# Boutconectie.net
KiCad netlist of a schematic drawn in Altium Designer
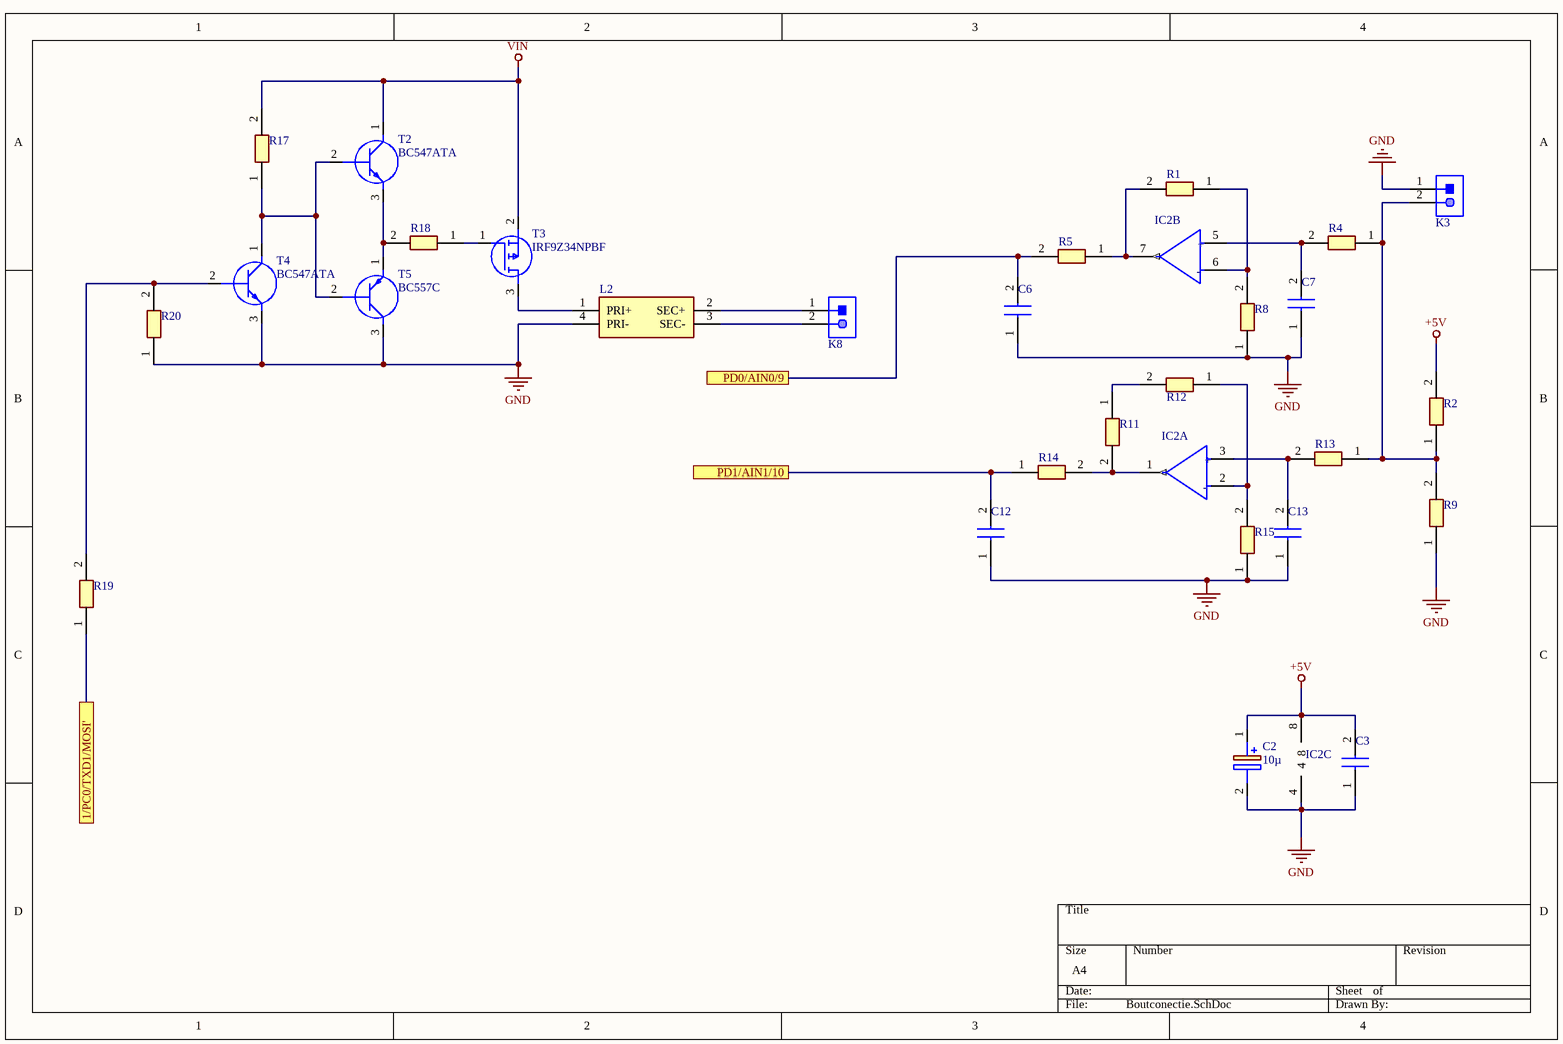
[diagram p0: Boutconectie.SchDoc]

(export (version "E")
  (design (tool "Eeschema 10.0.6"))
  (components
    (comp (ref "C2")
      (value "10µ")
      (footprint "SamacSys:CAPPRD200W52D500H1250")
      (description "Capacitor Polarised")
      (fields
        (field (name "MANUFACTURER_PART_NUMBER") "860010672009")
        (field (name "MOUSER PART NUMBER") "710-860010672009")
      )
      (libsource (lib "*") (part "860010672009"))
    )
    (comp (ref "C3")
      (value "~")
      (footprint "SamacSys:CAPC2012X95N")
      (description "Capacitor")
      (fields (field (name "MANUFACTURER_PART_NUMBER") "CC0805KPX7R9BB104"))
      (libsource (lib "*") (part "CC0805KPX7R9BB104"))
    )
    (comp (ref "C6")
      (value "~")
      (footprint "SamacSys:CAPC2012X95N")
      (description "Capacitor")
      (fields (field (name "MANUFACTURER_PART_NUMBER") "CC0805KPX7R9BB104"))
      (libsource (lib "*") (part "CC0805KPX7R9BB104"))
    )
    (comp (ref "C7")
      (value "~")
      (footprint "SamacSys:CAPC2012X95N")
      (description "Capacitor")
      (fields (field (name "MANUFACTURER_PART_NUMBER") "CC0805KPX7R9BB104"))
      (libsource (lib "*") (part "CC0805KPX7R9BB104"))
    )
    (comp (ref "C12")
      (value "~")
      (footprint "SamacSys:CAPC2012X95N")
      (description "Capacitor")
      (fields (field (name "MANUFACTURER_PART_NUMBER") "CC0805KPX7R9BB104"))
      (libsource (lib "*") (part "CC0805KPX7R9BB104"))
    )
    (comp (ref "C13")
      (value "~")
      (footprint "SamacSys:CAPC2012X95N")
      (description "Capacitor")
      (fields (field (name "MANUFACTURER_PART_NUMBER") "CC0805KPX7R9BB104"))
      (libsource (lib "*") (part "CC0805KPX7R9BB104"))
    )
    (comp (ref "IC2")
      (value "MCP6002-E_P")
      (footprint "SamacSys:DIP781W56P254L950H533Q8N")
      (description "Integrated Circuit")
      (fields
        (field (name "MANUFACTURER_PART_NUMBER") "MCP6002-E/P")
        (field (name "MOUSER PART NUMBER") "579-MCP6002-E/P")
      )
      (libsource (lib "SoldeerBoutLib") (part "MCP6002-E_P"))
    )
    (comp (ref "K3")
      (value "620102131822")
      (footprint "620102131822")
      (description "Male Shrouded Header WR-WTB, SMT, Right Angled, pitch 2 mm, 1 x 2 position")
      (fields (field (name "MANUFACTURER") "Wurth Elektronik") (field (name "PUBLISHER") "WurthElektronik"))
      (libsource (lib "Altium Content Vault") (part "WE-CN-1P-M-R2"))
    )
    (comp (ref "K8")
      (value "620102131822")
      (footprint "620102131822")
      (description "Male Shrouded Header WR-WTB, SMT, Right Angled, pitch 2 mm, 1 x 2 position")
      (fields (field (name "MANUFACTURER") "Wurth Elektronik") (field (name "PUBLISHER") "WurthElektronik"))
      (libsource (lib "Altium Content Vault") (part "WE-CN-1P-M-R2"))
    )
    (comp (ref "L2")
      (value "CM2545X171B-10")
      (footprint "SamacSys:CM2545X171B10")
      (description "Transformer")
      (libsource (lib "SoldeerBoutLib") (part "CM2545X171B-10"))
    )
    (comp (ref "R1")
      (value "~")
      (footprint "SamacSys:RESC2012X90N")
      (description "Resistor")
      (fields (field (name "MANUFACTURER_PART_NUMBER") "CFN0805-JZ-R010ELF"))
      (libsource (lib "SoldeerBoutLib") (part "CFN0805-JZ-R010ELF"))
    )
    (comp (ref "R2")
      (value "~")
      (footprint "SamacSys:RESC2012X90N")
      (description "Resistor")
      (fields (field (name "MANUFACTURER_PART_NUMBER") "CFN0805-JZ-R010ELF"))
      (libsource (lib "") (part "CFN0805-JZ-R010ELF_1"))
    )
    (comp (ref "R4")
      (value "~")
      (footprint "SamacSys:RESC2012X90N")
      (description "Resistor")
      (fields (field (name "MANUFACTURER_PART_NUMBER") "CFN0805-JZ-R010ELF"))
      (libsource (lib "SoldeerBoutLib") (part "CFN0805-JZ-R010ELF"))
    )
    (comp (ref "R5")
      (value "~")
      (footprint "SamacSys:RESC2012X90N")
      (description "Resistor")
      (fields (field (name "MANUFACTURER_PART_NUMBER") "CFN0805-JZ-R010ELF"))
      (libsource (lib "SoldeerBoutLib") (part "CFN0805-JZ-R010ELF"))
    )
    (comp (ref "R8")
      (value "~")
      (footprint "SamacSys:RESC2012X90N")
      (description "Resistor")
      (fields (field (name "MANUFACTURER_PART_NUMBER") "CFN0805-JZ-R010ELF"))
      (libsource (lib "") (part "CFN0805-JZ-R010ELF_1"))
    )
    (comp (ref "R9")
      (value "~")
      (footprint "SamacSys:RESC2012X90N")
      (description "Resistor")
      (fields (field (name "MANUFACTURER_PART_NUMBER") "CFN0805-JZ-R010ELF"))
      (libsource (lib "") (part "CFN0805-JZ-R010ELF_1"))
    )
    (comp (ref "R11")
      (value "~")
      (footprint "SamacSys:RESC2012X90N")
      (description "Resistor")
      (fields (field (name "MANUFACTURER_PART_NUMBER") "CFN0805-JZ-R010ELF"))
      (libsource (lib "") (part "CFN0805-JZ-R010ELF_2"))
    )
    (comp (ref "R12")
      (value "~")
      (footprint "SamacSys:RESC2012X90N")
      (description "Resistor")
      (fields (field (name "MANUFACTURER_PART_NUMBER") "CFN0805-JZ-R010ELF"))
      (libsource (lib "SoldeerBoutLib") (part "CFN0805-JZ-R010ELF"))
    )
    (comp (ref "R13")
      (value "~")
      (footprint "SamacSys:RESC2012X90N")
      (description "Resistor")
      (fields (field (name "MANUFACTURER_PART_NUMBER") "CFN0805-JZ-R010ELF"))
      (libsource (lib "SoldeerBoutLib") (part "CFN0805-JZ-R010ELF"))
    )
    (comp (ref "R14")
      (value "~")
      (footprint "SamacSys:RESC2012X90N")
      (description "Resistor")
      (fields (field (name "MANUFACTURER_PART_NUMBER") "CFN0805-JZ-R010ELF"))
      (libsource (lib "") (part "CFN0805-JZ-R010ELF_3"))
    )
    (comp (ref "R15")
      (value "~")
      (footprint "SamacSys:RESC2012X90N")
      (description "Resistor")
      (fields (field (name "MANUFACTURER_PART_NUMBER") "CFN0805-JZ-R010ELF"))
      (libsource (lib "") (part "CFN0805-JZ-R010ELF_1"))
    )
    (comp (ref "R17")
      (value "~")
      (footprint "SamacSys:RESC2012X90N")
      (description "Resistor")
      (fields (field (name "MANUFACTURER_PART_NUMBER") "CFN0805-JZ-R010ELF"))
      (libsource (lib "") (part "CFN0805-JZ-R010ELF_1"))
    )
    (comp (ref "R18")
      (value "~")
      (footprint "SamacSys:RESC2012X90N")
      (description "Resistor")
      (fields (field (name "MANUFACTURER_PART_NUMBER") "CFN0805-JZ-R010ELF"))
      (libsource (lib "SoldeerBoutLib") (part "CFN0805-JZ-R010ELF"))
    )
    (comp (ref "R19")
      (value "~")
      (footprint "SamacSys:RESC2012X90N")
      (description "Resistor")
      (fields (field (name "MANUFACTURER_PART_NUMBER") "CFN0805-JZ-R010ELF"))
      (libsource (lib "") (part "CFN0805-JZ-R010ELF_1"))
    )
    (comp (ref "R20")
      (value "~")
      (footprint "SamacSys:RESC2012X90N")
      (description "Resistor")
      (fields (field (name "MANUFACTURER_PART_NUMBER") "CFN0805-JZ-R010ELF"))
      (libsource (lib "") (part "CFN0805-JZ-R010ELF_1"))
    )
    (comp (ref "T2")
      (value "BC547ATA")
      (footprint "SamacSys:TO-92_(TO-226)")
      (description "Transistor BJT NPN")
      (fields (field (name "MOUSER PART NUMBER") "512-BC547ATA"))
      (libsource (lib "*") (part "BC547ATA"))
    )
    (comp (ref "T3")
      (value "IRF9Z34NPBF")
      (footprint "SamacSys:TO254P469X1042X1967-3P")
      (description "MOSFET (P-Channel)")
      (fields (field (name "MOUSER PART NUMBER") "942-IRF9Z34NPBF"))
      (libsource (lib "SoldeerBoutLib") (part "IRF9Z34NPBF"))
    )
    (comp (ref "T4")
      (value "BC547ATA")
      (footprint "SamacSys:TO-92_(TO-226)")
      (description "Transistor BJT NPN")
      (fields (field (name "MOUSER PART NUMBER") "512-BC547ATA"))
      (libsource (lib "*") (part "BC547ATA"))
    )
    (comp (ref "T5")
      (value "BC557C")
      (footprint "SamacSys:BC557C")
      (description "Transistor BJT PNP")
      (fields (field (name "MOUSER PART NUMBER") "771-BC557C"))
      (libsource (lib "SoldeerBoutLib") (part "BC557C"))
    )
  )
  (nets
    (net (code "1") (name "+5V") (class "Default")
      (node (ref "C2") (pin "1") (pinfunction "+_1") (pintype "passive"))
      (node (ref "C3") (pin "2") (pinfunction "2_2") (pintype "passive"))
      (node (ref "IC2") (pin "8") (pinfunction "8_8") (pintype "passive"))
      (node (ref "R2") (pin "2") (pinfunction "2_2") (pintype "passive"))
    )
    (net (code "2") (name "/1{slash}PC0{slash}TXD1{slash}MOSI'") (class "Default")
      (node (ref "R19") (pin "1") (pinfunction "1_1") (pintype "passive"))
    )
    (net (code "3") (name "/PD0{slash}AIN0{slash}9") (class "Default")
      (node (ref "C6") (pin "2") (pinfunction "2_2") (pintype "passive"))
      (node (ref "R5") (pin "2") (pinfunction "2_2") (pintype "passive"))
    )
    (net (code "4") (name "/PD1{slash}AIN1{slash}10") (class "Default")
      (node (ref "C12") (pin "2") (pinfunction "2_2") (pintype "passive"))
      (node (ref "R14") (pin "1") (pinfunction "1_1") (pintype "passive"))
    )
    (net (code "5") (name "GND") (class "Default")
      (node (ref "C12") (pin "1") (pinfunction "1_1") (pintype "passive"))
      (node (ref "C13") (pin "1") (pinfunction "1_1") (pintype "passive"))
      (node (ref "C2") (pin "2") (pinfunction "-_2") (pintype "passive"))
      (node (ref "C3") (pin "1") (pinfunction "1_1") (pintype "passive"))
      (node (ref "C6") (pin "1") (pinfunction "1_1") (pintype "passive"))
      (node (ref "C7") (pin "1") (pinfunction "1_1") (pintype "passive"))
      (node (ref "IC2") (pin "4") (pinfunction "4_4") (pintype "passive"))
      (node (ref "K3") (pin "1") (pinfunction "1_1") (pintype "passive"))
      (node (ref "L2") (pin "4") (pinfunction "PRI-_4") (pintype "passive"))
      (node (ref "R15") (pin "1") (pinfunction "1_1") (pintype "passive"))
      (node (ref "R20") (pin "1") (pinfunction "1_1") (pintype "passive"))
      (node (ref "R8") (pin "1") (pinfunction "1_1") (pintype "passive"))
      (node (ref "R9") (pin "1") (pinfunction "1_1") (pintype "passive"))
      (node (ref "T4") (pin "3") (pinfunction "E_3") (pintype "passive"))
      (node (ref "T5") (pin "3") (pinfunction "C_3") (pintype "passive"))
    )
    (net (code "6") (name "Net-(IC2A-2IN+)") (class "Default")
      (node (ref "C13") (pin "2") (pinfunction "2_2") (pintype "passive"))
      (node (ref "IC2") (pin "3") (pinfunction "2IN+_3") (pintype "tri_state"))
      (node (ref "R13") (pin "2") (pinfunction "2_2") (pintype "passive"))
    )
    (net (code "7") (name "Net-(IC2A-2IN-)") (class "Default")
      (node (ref "IC2") (pin "2") (pinfunction "2IN-_2") (pintype "tri_state"))
      (node (ref "R12") (pin "1") (pinfunction "1_1") (pintype "passive"))
      (node (ref "R15") (pin "2") (pinfunction "2_2") (pintype "passive"))
    )
    (net (code "8") (name "Net-(IC2A-2OUT)") (class "Default")
      (node (ref "IC2") (pin "1") (pinfunction "2OUT_1") (pintype "output"))
      (node (ref "R11") (pin "2") (pinfunction "2_2") (pintype "passive"))
      (node (ref "R14") (pin "2") (pinfunction "2_2") (pintype "passive"))
    )
    (net (code "9") (name "Net-(IC2B-2IN+)") (class "Default")
      (node (ref "C7") (pin "2") (pinfunction "2_2") (pintype "passive"))
      (node (ref "IC2") (pin "5") (pinfunction "2IN+_5") (pintype "tri_state"))
      (node (ref "R4") (pin "2") (pinfunction "2_2") (pintype "passive"))
    )
    (net (code "10") (name "Net-(IC2B-2IN-)") (class "Default")
      (node (ref "IC2") (pin "6") (pinfunction "2IN-_6") (pintype "tri_state"))
      (node (ref "R1") (pin "1") (pinfunction "1_1") (pintype "passive"))
      (node (ref "R8") (pin "2") (pinfunction "2_2") (pintype "passive"))
    )
    (net (code "11") (name "Net-(IC2B-2OUT)") (class "Default")
      (node (ref "IC2") (pin "7") (pinfunction "2OUT_7") (pintype "output"))
      (node (ref "R1") (pin "2") (pinfunction "2_2") (pintype "passive"))
      (node (ref "R5") (pin "1") (pinfunction "1_1") (pintype "passive"))
    )
    (net (code "12") (name "Net-(K3-Pad2)") (class "Default")
      (node (ref "K3") (pin "2") (pinfunction "2_2") (pintype "passive"))
      (node (ref "R13") (pin "1") (pinfunction "1_1") (pintype "passive"))
      (node (ref "R2") (pin "1") (pinfunction "1_1") (pintype "passive"))
      (node (ref "R4") (pin "1") (pinfunction "1_1") (pintype "passive"))
      (node (ref "R9") (pin "2") (pinfunction "2_2") (pintype "passive"))
    )
    (net (code "13") (name "Net-(L2-PRI+)") (class "Default")
      (node (ref "L2") (pin "1") (pinfunction "PRI+_1") (pintype "passive"))
      (node (ref "T3") (pin "3") (pinfunction "D_3") (pintype "passive"))
    )
    (net (code "14") (name "Net-(L2-SEC+)") (class "Default")
      (node (ref "K8") (pin "1") (pinfunction "1_1") (pintype "passive"))
      (node (ref "L2") (pin "2") (pinfunction "SEC+_2") (pintype "passive"))
    )
    (net (code "15") (name "Net-(L2-SEC-)") (class "Default")
      (node (ref "K8") (pin "2") (pinfunction "2_2") (pintype "passive"))
      (node (ref "L2") (pin "3") (pinfunction "SEC-_3") (pintype "passive"))
    )
    (net (code "16") (name "Net-(R11-Pad1)") (class "Default")
      (node (ref "R11") (pin "1") (pinfunction "1_1") (pintype "passive"))
      (node (ref "R12") (pin "2") (pinfunction "2_2") (pintype "passive"))
    )
    (net (code "17") (name "Net-(T2-B)") (class "Default")
      (node (ref "R17") (pin "1") (pinfunction "1_1") (pintype "passive"))
      (node (ref "T2") (pin "2") (pinfunction "B_2") (pintype "passive"))
      (node (ref "T4") (pin "1") (pinfunction "C_1") (pintype "passive"))
      (node (ref "T5") (pin "2") (pinfunction "B_2") (pintype "passive"))
    )
    (net (code "18") (name "Net-(T2-E)") (class "Default")
      (node (ref "R18") (pin "2") (pinfunction "2_2") (pintype "passive"))
      (node (ref "T2") (pin "3") (pinfunction "E_3") (pintype "passive"))
      (node (ref "T5") (pin "1") (pinfunction "E_1") (pintype "passive"))
    )
    (net (code "19") (name "Net-(T3-G)") (class "Default")
      (node (ref "R18") (pin "1") (pinfunction "1_1") (pintype "passive"))
      (node (ref "T3") (pin "1") (pinfunction "G_1") (pintype "passive"))
    )
    (net (code "20") (name "Net-(T4-B)") (class "Default")
      (node (ref "R19") (pin "2") (pinfunction "2_2") (pintype "passive"))
      (node (ref "R20") (pin "2") (pinfunction "2_2") (pintype "passive"))
      (node (ref "T4") (pin "2") (pinfunction "B_2") (pintype "passive"))
    )
    (net (code "21") (name "VIN") (class "Default")
      (node (ref "R17") (pin "2") (pinfunction "2_2") (pintype "passive"))
      (node (ref "T2") (pin "1") (pinfunction "C_1") (pintype "passive"))
      (node (ref "T3") (pin "2") (pinfunction "S_2") (pintype "passive"))
    )
  )
)
